# CCProgrammer.net
KiCad netlist of a schematic drawn in EAGLE
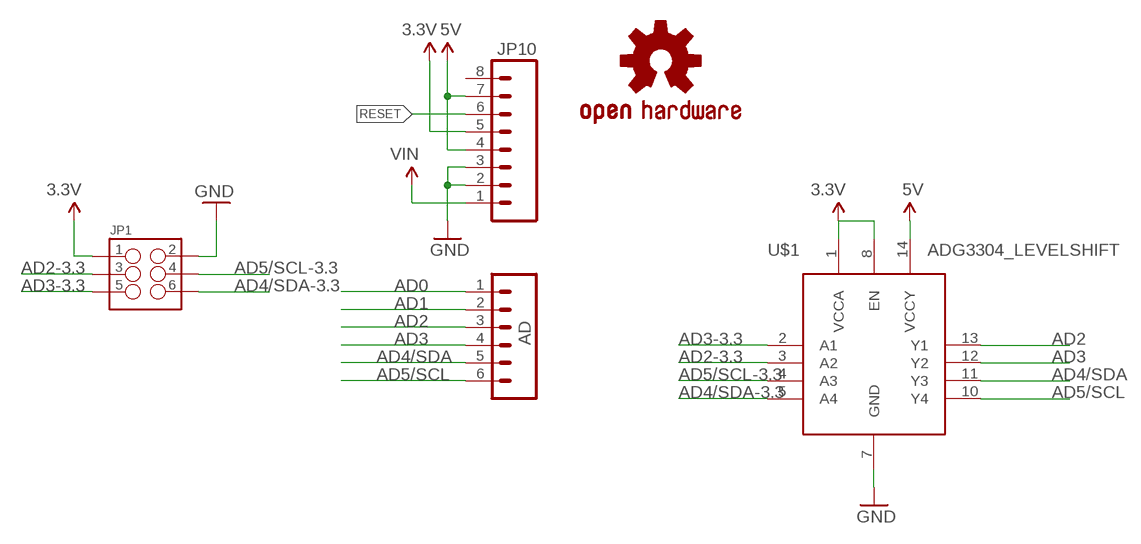
[diagram p0: schematic, sheet 1]

(export (version "E")
  (design (tool "Eeschema 10.0.6"))
  (components
    (comp (ref "AD")
      (value "M06SMD-STRAIGHT-COMBO")
      (footprint "eagle-import:1X06_SMD_STRAIGHT_COMBO")
      (libsource (lib "eagle-import") (part "M06SMD-STRAIGHT-COMBO"))
    )
    (comp (ref "JP1")
      (value "M03X2SHROUD")
      (footprint "eagle-import:2X3-SHROUDED")
      (libsource (lib "eagle-import") (part "M03X2SHROUD"))
    )
    (comp (ref "JP10")
      (value "M08SMD-COMBO")
      (footprint "eagle-import:1X08_SMD_COMBINED")
      (libsource (lib "eagle-import") (part "M08SMD-COMBO"))
    )
    (comp (ref "LOGO1")
      (value "OSHW-LOGOM")
      (footprint "eagle-import:OSHW-LOGO-M")
      (libsource (lib "eagle-import") (part "OSHW-LOGOM"))
    )
    (comp (ref "U$1")
      (value "ADG3304_LEVELSHIFT")
      (footprint "eagle-import:TSSOP14_0.65MM_4.4MM")
      (libsource (lib "eagle-import") (part "ADG3304_LEVELSHIFT"))
    )
  )
  (nets
    (net (code "1") (name "/AD0") (class "Default")
      (node (ref "AD") (pin "1") (pinfunction "1_1") (pintype "passive"))
    )
    (net (code "2") (name "/AD1") (class "Default")
      (node (ref "AD") (pin "2") (pinfunction "2_2") (pintype "passive"))
    )
    (net (code "3") (name "/AD2") (class "Default")
      (node (ref "AD") (pin "3") (pinfunction "3_3") (pintype "passive"))
      (node (ref "U$1") (pin "13") (pinfunction "Y1_13") (pintype "bidirectional"))
    )
    (net (code "4") (name "/AD2-3.3") (class "Default")
      (node (ref "JP1") (pin "3") (pinfunction "3_3") (pintype "bidirectional"))
      (node (ref "U$1") (pin "3") (pinfunction "A2_3") (pintype "bidirectional"))
    )
    (net (code "5") (name "/AD3") (class "Default")
      (node (ref "AD") (pin "4") (pinfunction "4_4") (pintype "passive"))
      (node (ref "U$1") (pin "12") (pinfunction "Y2_12") (pintype "bidirectional"))
    )
    (net (code "6") (name "/AD3-3.3") (class "Default")
      (node (ref "JP1") (pin "5") (pinfunction "5_5") (pintype "bidirectional"))
      (node (ref "U$1") (pin "2") (pinfunction "A1_2") (pintype "bidirectional"))
    )
    (net (code "7") (name "/AD4{slash}SDA") (class "Default")
      (node (ref "AD") (pin "5") (pinfunction "5_5") (pintype "passive"))
      (node (ref "U$1") (pin "11") (pinfunction "Y3_11") (pintype "bidirectional"))
    )
    (net (code "8") (name "/AD4{slash}SDA-3.3") (class "Default")
      (node (ref "JP1") (pin "6") (pinfunction "6_6") (pintype "bidirectional"))
      (node (ref "U$1") (pin "5") (pinfunction "A4_5") (pintype "bidirectional"))
    )
    (net (code "9") (name "/AD5{slash}SCL") (class "Default")
      (node (ref "AD") (pin "6") (pinfunction "6_6") (pintype "passive"))
      (node (ref "U$1") (pin "10") (pinfunction "Y4_10") (pintype "bidirectional"))
    )
    (net (code "10") (name "/AD5{slash}SCL-3.3") (class "Default")
      (node (ref "JP1") (pin "4") (pinfunction "4_4") (pintype "bidirectional"))
      (node (ref "U$1") (pin "4") (pinfunction "A3_4") (pintype "bidirectional"))
    )
    (net (code "11") (name "3.3V") (class "Default")
      (node (ref "JP1") (pin "1") (pinfunction "1_1") (pintype "bidirectional"))
      (node (ref "JP10") (pin "5") (pinfunction "5_5") (pintype "passive"))
      (node (ref "U$1") (pin "1") (pinfunction "VCCA_1") (pintype "bidirectional"))
      (node (ref "U$1") (pin "8") (pinfunction "EN_8") (pintype "bidirectional"))
    )
    (net (code "12") (name "5V") (class "Default")
      (node (ref "JP10") (pin "4") (pinfunction "4_4") (pintype "passive"))
      (node (ref "JP10") (pin "7") (pinfunction "7_7") (pintype "passive"))
      (node (ref "U$1") (pin "14") (pinfunction "VCCY_14") (pintype "bidirectional"))
    )
    (net (code "13") (name "GND") (class "Default")
      (node (ref "JP1") (pin "2") (pinfunction "2_2") (pintype "bidirectional"))
      (node (ref "JP10") (pin "2") (pinfunction "2_2") (pintype "passive"))
      (node (ref "JP10") (pin "3") (pinfunction "3_3") (pintype "passive"))
      (node (ref "U$1") (pin "7") (pinfunction "GND_7") (pintype "bidirectional"))
    )
    (net (code "14") (name "RESET") (class "Default")
      (node (ref "JP10") (pin "6") (pinfunction "6_6") (pintype "passive"))
    )
    (net (code "15") (name "VIN") (class "Default")
      (node (ref "JP10") (pin "1") (pinfunction "1_1") (pintype "passive"))
    )
    (net (code "16") (name "unconnected-(JP10-Pad8)") (class "Default")
      (node (ref "JP10") (pin "8") (pinfunction "8_8") (pintype "passive"))
    )
  )
)
